# msp430_round.net
KiCad netlist of a schematic drawn in EAGLE
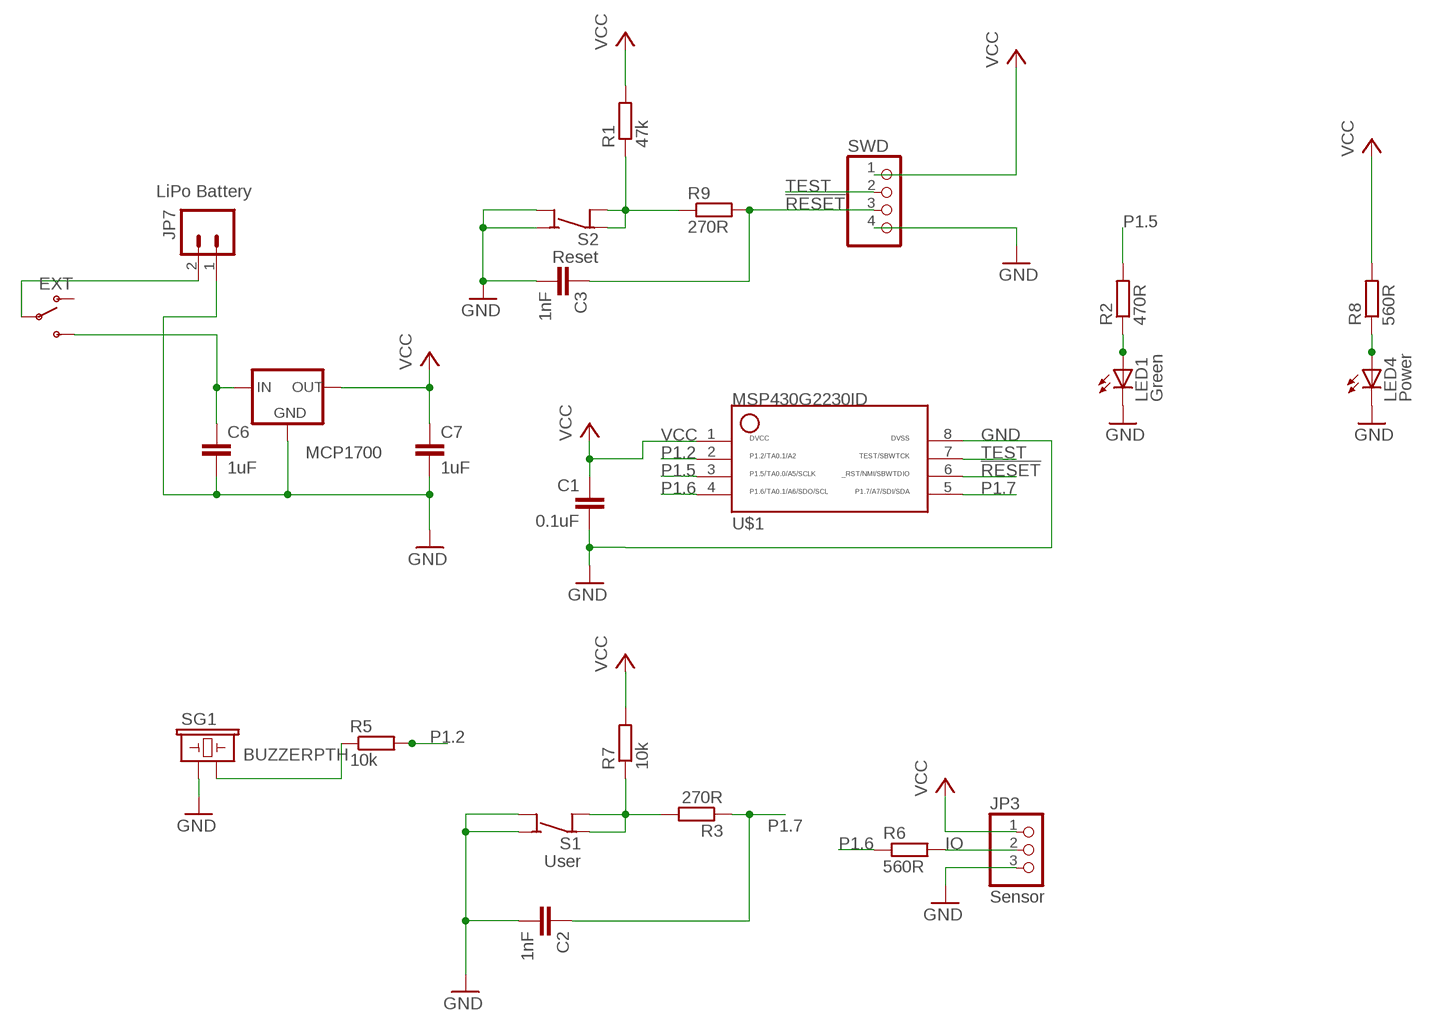
[diagram p0: schematic, sheet 1]

(export (version "E")
  (design (tool "Eeschema 10.0.6"))
  (components
    (comp (ref "C1")
      (value "0.1uF")
      (footprint "eagle-import:C0805")
      (libsource (lib "eagle-import") (part "C-EUC0805"))
    )
    (comp (ref "C2")
      (value "1nF")
      (footprint "eagle-import:C0805")
      (libsource (lib "eagle-import") (part "C-EUC0805"))
    )
    (comp (ref "C3")
      (value "1nF")
      (footprint "eagle-import:C0805")
      (libsource (lib "eagle-import") (part "C-EUC0805"))
    )
    (comp (ref "C6")
      (value "1uF")
      (footprint "eagle-import:C0805")
      (libsource (lib "eagle-import") (part "C-EUC0805"))
    )
    (comp (ref "C7")
      (value "1uF")
      (footprint "eagle-import:C0805")
      (libsource (lib "eagle-import") (part "C-EUC0805"))
    )
    (comp (ref "JP3")
      (value "Sensor")
      (footprint "eagle-import:1X03")
      (libsource (lib "eagle-import") (part "PINHD-1X3"))
    )
    (comp (ref "JP7")
      (value "LiPo Battery")
      (footprint "eagle-import:JST-2-PTH")
      (libsource (lib "eagle-import") (part "M02JST-PTH-2"))
    )
    (comp (ref "LED1")
      (value "Green")
      (footprint "eagle-import:CHIPLED_1206")
      (libsource (lib "eagle-import") (part "LEDCHIPLED_1206"))
    )
    (comp (ref "LED4")
      (value "Power")
      (footprint "eagle-import:CHIPLED_1206")
      (libsource (lib "eagle-import") (part "LEDCHIPLED_1206"))
    )
    (comp (ref "MCP1700")
      (value "MCP1700")
      (footprint "eagle-import:SOT-23")
      (libsource (lib "eagle-import") (part "MCP1700SOT-23"))
    )
    (comp (ref "ON")
      (value "EXT")
      (footprint "eagle-import:SWITCH-SPDT")
      (libsource (lib "eagle-import") (part "SWITCH-SPSTPTH"))
    )
    (comp (ref "R1")
      (value "47k")
      (footprint "eagle-import:R0805")
      (libsource (lib "eagle-import") (part "R-EU_R0805"))
    )
    (comp (ref "R2")
      (value "470R")
      (footprint "eagle-import:R0805")
      (libsource (lib "eagle-import") (part "R-EU_R0805"))
    )
    (comp (ref "R3")
      (value "270R")
      (footprint "eagle-import:R0805")
      (libsource (lib "eagle-import") (part "R-EU_R0805"))
    )
    (comp (ref "R5")
      (value "10k")
      (footprint "eagle-import:R0805")
      (libsource (lib "eagle-import") (part "R-EU_R0805"))
    )
    (comp (ref "R6")
      (value "560R")
      (footprint "eagle-import:R0805")
      (libsource (lib "eagle-import") (part "R-EU_R0805"))
    )
    (comp (ref "R7")
      (value "10k")
      (footprint "eagle-import:R0805")
      (libsource (lib "eagle-import") (part "R-EU_R0805"))
    )
    (comp (ref "R8")
      (value "560R")
      (footprint "eagle-import:R0805")
      (libsource (lib "eagle-import") (part "R-EU_R0805"))
    )
    (comp (ref "R9")
      (value "270R")
      (footprint "eagle-import:R0805")
      (libsource (lib "eagle-import") (part "R-EU_R0805"))
    )
    (comp (ref "S1")
      (value "User")
      (footprint "eagle-import:6MMTACTILE_4PIN")
      (libsource (lib "eagle-import") (part "SPST4"))
    )
    (comp (ref "S2")
      (value "Reset")
      (footprint "eagle-import:6MMTACTILE_4PIN")
      (libsource (lib "eagle-import") (part "SPST4"))
    )
    (comp (ref "SG1")
      (value "BUZZERPTH")
      (footprint "eagle-import:BUZZER-12MM")
      (libsource (lib "eagle-import") (part "BUZZERPTH"))
    )
    (comp (ref "SWD")
      (value "PINHD-1X4")
      (footprint "eagle-import:1X04")
      (libsource (lib "eagle-import") (part "PINHD-1X4"))
    )
    (comp (ref "U$1")
      (value "MSP430G2230ID")
      (footprint "eagle-import:SO08")
      (libsource (lib "eagle-import") (part "MSP430G2230ID"))
    )
  )
  (nets
    (net (code "1") (name "/IO") (class "Default")
      (node (ref "JP3") (pin "2") (pinfunction "2_2") (pintype "passive"))
      (node (ref "R6") (pin "2") (pinfunction "2_2") (pintype "passive"))
    )
    (net (code "2") (name "/P1.2") (class "Default")
      (node (ref "R5") (pin "2") (pinfunction "2_2") (pintype "passive"))
      (node (ref "U$1") (pin "2") (pinfunction "2_2") (pintype "bidirectional"))
    )
    (net (code "3") (name "/P1.5") (class "Default")
      (node (ref "R2") (pin "2") (pinfunction "2_2") (pintype "passive"))
      (node (ref "U$1") (pin "3") (pinfunction "3_3") (pintype "bidirectional"))
    )
    (net (code "4") (name "/P1.6") (class "Default")
      (node (ref "R6") (pin "1") (pinfunction "1_1") (pintype "passive"))
      (node (ref "U$1") (pin "4") (pinfunction "4_4") (pintype "bidirectional"))
    )
    (net (code "5") (name "/P1.7") (class "Default")
      (node (ref "C2") (pin "1") (pinfunction "1_1") (pintype "passive"))
      (node (ref "R3") (pin "1") (pinfunction "1_1") (pintype "passive"))
      (node (ref "U$1") (pin "5") (pinfunction "5_5") (pintype "bidirectional"))
    )
    (net (code "6") (name "/TEST") (class "Default")
      (node (ref "SWD") (pin "2") (pinfunction "2_2") (pintype "passive"))
      (node (ref "U$1") (pin "7") (pinfunction "7_7") (pintype "bidirectional"))
    )
    (net (code "7") (name "/~{RESET}") (class "Default")
      (node (ref "C3") (pin "1") (pinfunction "1_1") (pintype "passive"))
      (node (ref "R9") (pin "2") (pinfunction "2_2") (pintype "passive"))
      (node (ref "SWD") (pin "3") (pinfunction "3_3") (pintype "passive"))
      (node (ref "U$1") (pin "6") (pinfunction "6_6") (pintype "bidirectional"))
    )
    (net (code "8") (name "GND") (class "Default")
      (node (ref "C1") (pin "2") (pinfunction "2_2") (pintype "passive"))
      (node (ref "C2") (pin "2") (pinfunction "2_2") (pintype "passive"))
      (node (ref "C3") (pin "2") (pinfunction "2_2") (pintype "passive"))
      (node (ref "C6") (pin "2") (pinfunction "2_2") (pintype "passive"))
      (node (ref "C7") (pin "2") (pinfunction "2_2") (pintype "passive"))
      (node (ref "JP3") (pin "3") (pinfunction "3_3") (pintype "passive"))
      (node (ref "JP7") (pin "1") (pinfunction "1_1") (pintype "passive"))
      (node (ref "LED1") (pin "C") (pinfunction "C_C") (pintype "passive"))
      (node (ref "LED4") (pin "C") (pinfunction "C_C") (pintype "passive"))
      (node (ref "MCP1700") (pin "1") (pinfunction "GND_1") (pintype "input"))
      (node (ref "S1") (pin "A1") (pinfunction "NO_A1") (pintype "passive"))
      (node (ref "S1") (pin "A2") (pinfunction "NO_A2") (pintype "passive"))
      (node (ref "S2") (pin "A1") (pinfunction "NO_A1") (pintype "passive"))
      (node (ref "S2") (pin "A2") (pinfunction "NO_A2") (pintype "passive"))
      (node (ref "SG1") (pin "+") (pinfunction "1_+") (pintype "passive"))
      (node (ref "SWD") (pin "4") (pinfunction "4_4") (pintype "passive"))
      (node (ref "U$1") (pin "8") (pinfunction "8_8") (pintype "power_in"))
    )
    (net (code "9") (name "Net-(LED1-PadA)") (class "Default")
      (node (ref "LED1") (pin "A") (pinfunction "A_A") (pintype "passive"))
      (node (ref "R2") (pin "1") (pinfunction "1_1") (pintype "passive"))
    )
    (net (code "10") (name "Net-(LED4-PadA)") (class "Default")
      (node (ref "LED4") (pin "A") (pinfunction "A_A") (pintype "passive"))
      (node (ref "R8") (pin "1") (pinfunction "1_1") (pintype "passive"))
    )
    (net (code "11") (name "Net-(MCP1700-IN)") (class "Default")
      (node (ref "C6") (pin "1") (pinfunction "1_1") (pintype "passive"))
      (node (ref "MCP1700") (pin "3") (pinfunction "IN_3") (pintype "input"))
      (node (ref "ON") (pin "3") (pinfunction "S_3") (pintype "passive"))
    )
    (net (code "12") (name "Net-(ON-P)") (class "Default")
      (node (ref "JP7") (pin "2") (pinfunction "2_2") (pintype "passive"))
      (node (ref "ON") (pin "2") (pinfunction "P_2") (pintype "passive"))
    )
    (net (code "13") (name "Net-(R1-Pad1)") (class "Default")
      (node (ref "R1") (pin "1") (pinfunction "1_1") (pintype "passive"))
      (node (ref "R9") (pin "1") (pinfunction "1_1") (pintype "passive"))
      (node (ref "S2") (pin "B1") (pinfunction "COM_B1") (pintype "passive"))
      (node (ref "S2") (pin "B2") (pinfunction "COM_B2") (pintype "passive"))
    )
    (net (code "14") (name "Net-(R3-Pad2)") (class "Default")
      (node (ref "R3") (pin "2") (pinfunction "2_2") (pintype "passive"))
      (node (ref "R7") (pin "1") (pinfunction "1_1") (pintype "passive"))
      (node (ref "S1") (pin "B1") (pinfunction "COM_B1") (pintype "passive"))
      (node (ref "S1") (pin "B2") (pinfunction "COM_B2") (pintype "passive"))
    )
    (net (code "15") (name "Net-(SG1-2)") (class "Default")
      (node (ref "R5") (pin "1") (pinfunction "1_1") (pintype "passive"))
      (node (ref "SG1") (pin "-") (pinfunction "2_-") (pintype "passive"))
    )
    (net (code "16") (name "VCC") (class "Default")
      (node (ref "C1") (pin "1") (pinfunction "1_1") (pintype "passive"))
      (node (ref "C7") (pin "1") (pinfunction "1_1") (pintype "passive"))
      (node (ref "JP3") (pin "1") (pinfunction "1_1") (pintype "passive"))
      (node (ref "MCP1700") (pin "2") (pinfunction "OUT_2") (pintype "passive"))
      (node (ref "R1") (pin "2") (pinfunction "2_2") (pintype "passive"))
      (node (ref "R7") (pin "2") (pinfunction "2_2") (pintype "passive"))
      (node (ref "R8") (pin "2") (pinfunction "2_2") (pintype "passive"))
      (node (ref "SWD") (pin "1") (pinfunction "1_1") (pintype "passive"))
      (node (ref "U$1") (pin "1") (pinfunction "1_1") (pintype "power_in"))
    )
    (net (code "17") (name "unconnected-(ON-O-Pad1)") (class "Default")
      (node (ref "ON") (pin "1") (pinfunction "O_1") (pintype "passive"))
    )
  )
)
